# SCH_spponpcbfin_2024-06-20.net
KiCad netlist of a schematic drawn in EasyEDA
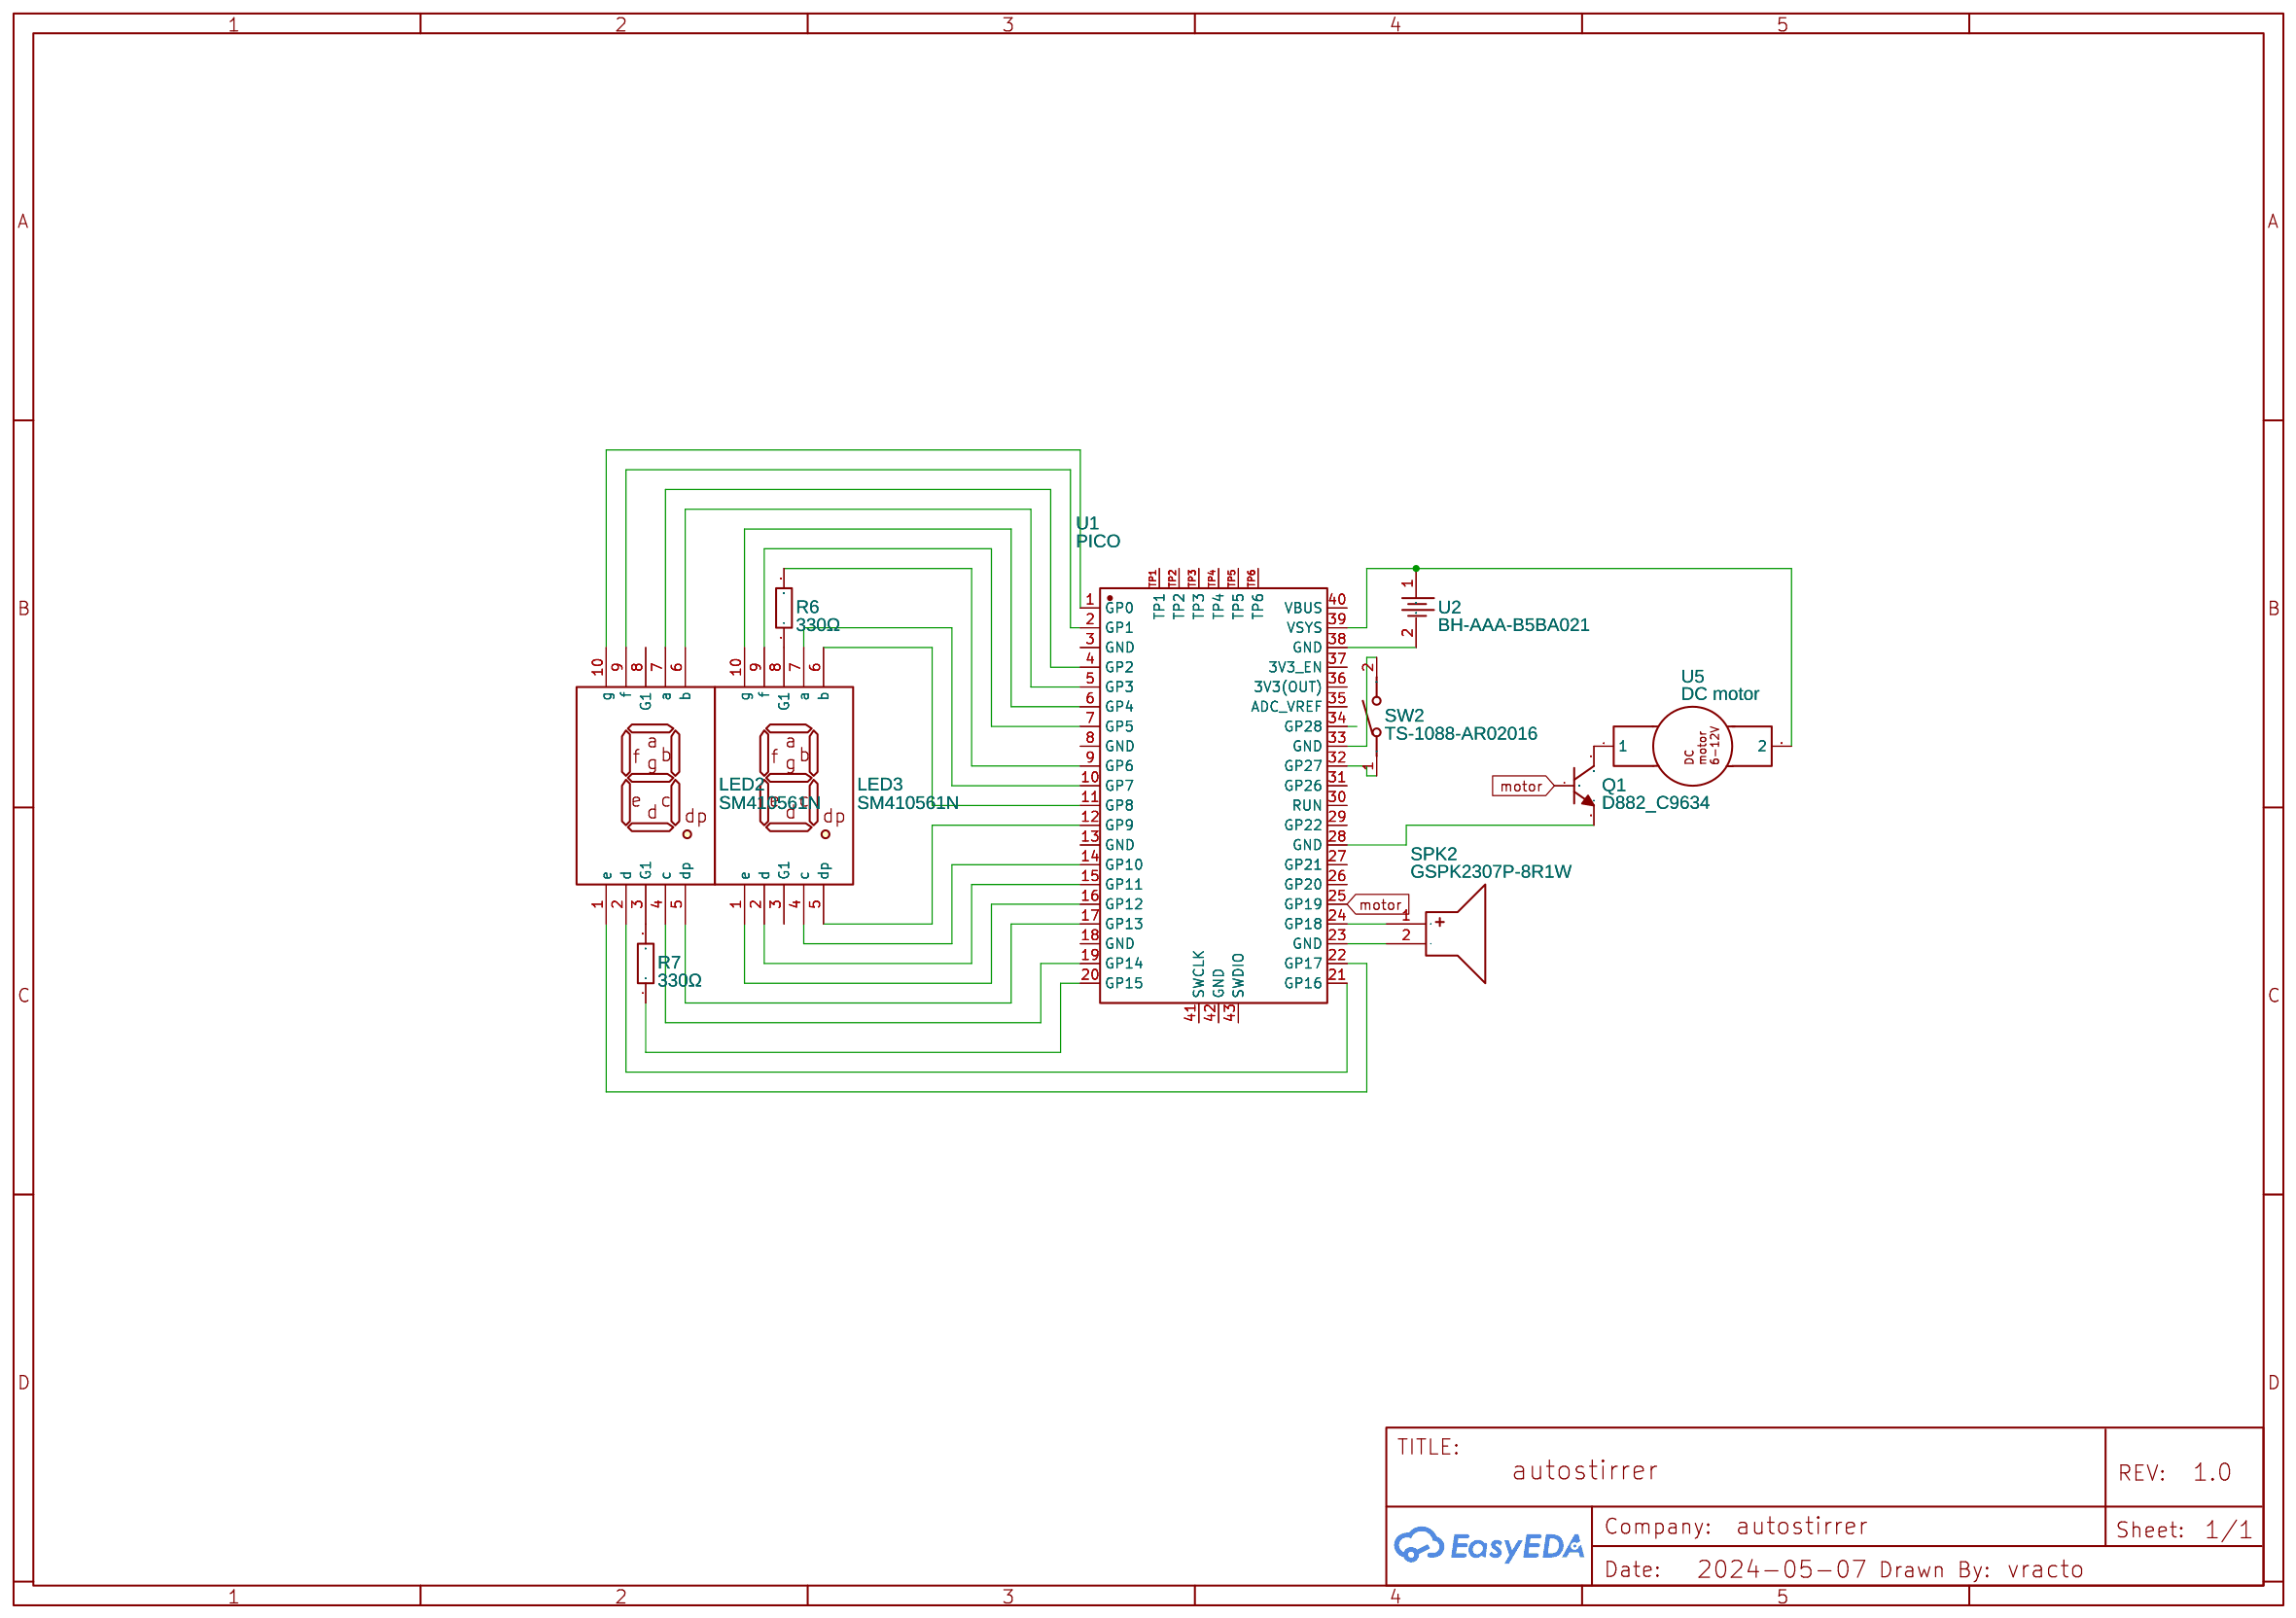
[diagram p0: schematic sheet]

(export (version "E")
  (design (tool "Eeschema 10.0.6"))
  (components
    (comp (ref "LED2")
      (value "SM410561N")
      (fields (field (name "Manufacturer") "ARKLED(方舟)"))
      (libsource (lib "") (part "SM410561N"))
    )
    (comp (ref "LED3")
      (value "SM410561N")
      (fields (field (name "Manufacturer") "ARKLED(方舟)"))
      (libsource (lib "") (part "SM410561N"))
    )
    (comp (ref "Q1")
      (value "D882_C9634")
      (fields
        (field (name "Manufacturer Part") "D882 Y档160&#126;320")
        (field (name "Manufacturer") "CJ(江苏长电/长晶)")
      )
      (libsource (lib "") (part "D882_C9634"))
    )
    (comp (ref "R6")
      (value "330Ω")
      (fields (field (name "Manufacturer Part") "MFR-25FTE52-330R") (field (name "Manufacturer") "YAGEO(国巨)"))
      (libsource (lib "") (part "MFR-25FTE52-330R"))
    )
    (comp (ref "R7")
      (value "330Ω")
      (fields (field (name "Manufacturer Part") "MFR-25FTE52-330R") (field (name "Manufacturer") "YAGEO(国巨)"))
      (libsource (lib "") (part "MFR-25FTE52-330R"))
    )
    (comp (ref "SPK2")
      (value "GSPK2307P-8R1W")
      (fields (field (name "Manufacturer") "INGHAi(赢海)"))
      (libsource (lib "") (part "GSPK2307P-8R1W"))
    )
    (comp (ref "SW2")
      (value "TS-1088-AR02016")
      (fields (field (name "Manufacturer") "XUNPU(讯普)"))
      (libsource (lib "") (part "TS-1088-AR02016"))
    )
    (comp (ref "U1")
      (value "PICO")
      (fields (field (name "Manufacturer") "Raspberry Pi(树莓派)"))
      (libsource (lib "") (part "PICO"))
    )
    (comp (ref "U2")
      (value "BH-AAA-B5BA021")
      (fields (field (name "Manufacturer") "MYOUNG(美阳)"))
      (libsource (lib "") (part "BH-AAA-B5BA021"))
    )
    (comp (ref "U5")
      (value "DC motor")
      (fields (field (name "Manufacturer Part") "?"))
      (libsource (lib "") (part "Unknown_850_-435"))
    )
  )
  (nets
    (net (code "1") (name "Net-(LED2-G1-Pad3)") (class "Default")
      (node (ref "LED2") (pin "3") (pinfunction "G1_3") (pintype "input"))
      (node (ref "R7") (pin "2") (pinfunction "2_2") (pintype "input"))
    )
    (net (code "2") (name "Net-(LED2-a)") (class "Default")
      (node (ref "LED2") (pin "7") (pinfunction "a_7") (pintype "input"))
      (node (ref "U1") (pin "4") (pinfunction "GP2_4") (pintype "unspecified"))
    )
    (net (code "3") (name "Net-(LED2-b)") (class "Default")
      (node (ref "LED2") (pin "6") (pinfunction "b_6") (pintype "input"))
      (node (ref "U1") (pin "5") (pinfunction "GP3_5") (pintype "unspecified"))
    )
    (net (code "4") (name "Net-(LED2-c)") (class "Default")
      (node (ref "LED2") (pin "4") (pinfunction "c_4") (pintype "input"))
      (node (ref "U1") (pin "19") (pinfunction "GP14_19") (pintype "unspecified"))
    )
    (net (code "5") (name "Net-(LED2-d)") (class "Default")
      (node (ref "LED2") (pin "2") (pinfunction "d_2") (pintype "input"))
      (node (ref "U1") (pin "21") (pinfunction "GP16_21") (pintype "unspecified"))
    )
    (net (code "6") (name "Net-(LED2-dp)") (class "Default")
      (node (ref "LED2") (pin "5") (pinfunction "dp_5") (pintype "input"))
      (node (ref "U1") (pin "17") (pinfunction "GP13_17") (pintype "unspecified"))
    )
    (net (code "7") (name "Net-(LED2-e)") (class "Default")
      (node (ref "LED2") (pin "1") (pinfunction "e_1") (pintype "input"))
      (node (ref "U1") (pin "22") (pinfunction "GP17_22") (pintype "unspecified"))
    )
    (net (code "8") (name "Net-(LED2-f)") (class "Default")
      (node (ref "LED2") (pin "9") (pinfunction "f_9") (pintype "input"))
      (node (ref "U1") (pin "2") (pinfunction "GP1_2") (pintype "unspecified"))
    )
    (net (code "9") (name "Net-(LED2-g)") (class "Default")
      (node (ref "LED2") (pin "10") (pinfunction "g_10") (pintype "input"))
      (node (ref "U1") (pin "1") (pinfunction "GP0_1") (pintype "unspecified"))
    )
    (net (code "10") (name "Net-(LED3-G1-Pad8)") (class "Default")
      (node (ref "LED3") (pin "8") (pinfunction "G1_8") (pintype "input"))
      (node (ref "R6") (pin "1") (pinfunction "1_1") (pintype "input"))
    )
    (net (code "11") (name "Net-(LED3-a)") (class "Default")
      (node (ref "LED3") (pin "7") (pinfunction "a_7") (pintype "input"))
      (node (ref "U1") (pin "10") (pinfunction "GP7_10") (pintype "unspecified"))
    )
    (net (code "12") (name "Net-(LED3-b)") (class "Default")
      (node (ref "LED3") (pin "6") (pinfunction "b_6") (pintype "input"))
      (node (ref "U1") (pin "11") (pinfunction "GP8_11") (pintype "unspecified"))
    )
    (net (code "13") (name "Net-(LED3-c)") (class "Default")
      (node (ref "LED3") (pin "4") (pinfunction "c_4") (pintype "input"))
      (node (ref "U1") (pin "14") (pinfunction "GP10_14") (pintype "unspecified"))
    )
    (net (code "14") (name "Net-(LED3-d)") (class "Default")
      (node (ref "LED3") (pin "2") (pinfunction "d_2") (pintype "input"))
      (node (ref "U1") (pin "15") (pinfunction "GP11_15") (pintype "unspecified"))
    )
    (net (code "15") (name "Net-(LED3-dp)") (class "Default")
      (node (ref "LED3") (pin "5") (pinfunction "dp_5") (pintype "input"))
      (node (ref "U1") (pin "12") (pinfunction "GP9_12") (pintype "unspecified"))
    )
    (net (code "16") (name "Net-(LED3-e)") (class "Default")
      (node (ref "LED3") (pin "1") (pinfunction "e_1") (pintype "input"))
      (node (ref "U1") (pin "16") (pinfunction "GP12_16") (pintype "unspecified"))
    )
    (net (code "17") (name "Net-(LED3-f)") (class "Default")
      (node (ref "LED3") (pin "9") (pinfunction "f_9") (pintype "input"))
      (node (ref "U1") (pin "7") (pinfunction "GP5_7") (pintype "unspecified"))
    )
    (net (code "18") (name "Net-(LED3-g)") (class "Default")
      (node (ref "LED3") (pin "10") (pinfunction "g_10") (pintype "input"))
      (node (ref "U1") (pin "6") (pinfunction "GP4_6") (pintype "unspecified"))
    )
    (net (code "19") (name "Net-(Q1-C)") (class "Default")
      (node (ref "Q1") (pin "2") (pinfunction "C_2") (pintype "input"))
      (node (ref "U5") (pin "1") (pinfunction "1_1") (pintype "unspecified"))
    )
    (net (code "20") (name "Net-(Q1-E)") (class "Default")
      (node (ref "Q1") (pin "3") (pinfunction "E_3") (pintype "input"))
      (node (ref "U1") (pin "28") (pinfunction "GND_28") (pintype "unspecified"))
    )
    (net (code "21") (name "Net-(SPK2-+)") (class "Default")
      (node (ref "SPK2") (pin "1") (pinfunction "+_1") (pintype "unspecified"))
      (node (ref "U1") (pin "24") (pinfunction "GP18_24") (pintype "unspecified"))
    )
    (net (code "22") (name "Net-(SPK2--)") (class "Default")
      (node (ref "SPK2") (pin "2") (pinfunction "-_2") (pintype "unspecified"))
      (node (ref "U1") (pin "23") (pinfunction "GND_23") (pintype "unspecified"))
    )
    (net (code "23") (name "Net-(SW2-Pad2)") (class "Default")
      (node (ref "SW2") (pin "2") (pinfunction "2_2") (pintype "unspecified"))
      (node (ref "U1") (pin "33") (pinfunction "GND_33") (pintype "unspecified"))
    )
    (net (code "24") (name "Net-(U1-GND-Pad38)") (class "Default")
      (node (ref "U1") (pin "38") (pinfunction "GND_38") (pintype "unspecified"))
      (node (ref "U2") (pin "2") (pinfunction "2_2") (pintype "input"))
    )
    (net (code "25") (name "Net-(U1-GP6)") (class "Default")
      (node (ref "R6") (pin "2") (pinfunction "2_2") (pintype "input"))
      (node (ref "U1") (pin "9") (pinfunction "GP6_9") (pintype "unspecified"))
    )
    (net (code "26") (name "Net-(U1-GP15)") (class "Default")
      (node (ref "R7") (pin "1") (pinfunction "1_1") (pintype "input"))
      (node (ref "U1") (pin "20") (pinfunction "GP15_20") (pintype "unspecified"))
    )
    (net (code "27") (name "Net-(U1-GP27)") (class "Default")
      (node (ref "SW2") (pin "1") (pinfunction "1_1") (pintype "unspecified"))
      (node (ref "U1") (pin "32") (pinfunction "GP27_32") (pintype "unspecified"))
    )
    (net (code "28") (name "Net-(U1-VSYS)") (class "Default")
      (node (ref "U1") (pin "39") (pinfunction "VSYS_39") (pintype "unspecified"))
      (node (ref "U2") (pin "1") (pinfunction "1_1") (pintype "input"))
      (node (ref "U5") (pin "2") (pinfunction "2_2") (pintype "unspecified"))
    )
    (net (code "29") (name "motor") (class "Default")
      (node (ref "Q1") (pin "1") (pinfunction "B_1") (pintype "input"))
      (node (ref "U1") (pin "25") (pinfunction "GP19_25") (pintype "unspecified"))
    )
    (net (code "30") (name "unconnected-(LED2-G1-Pad8)") (class "Default")
      (node (ref "LED2") (pin "8") (pinfunction "G1_8") (pintype "input"))
    )
    (net (code "31") (name "unconnected-(LED3-G1-Pad3)") (class "Default")
      (node (ref "LED3") (pin "3") (pinfunction "G1_3") (pintype "input"))
    )
    (net (code "32") (name "unconnected-(U1-3V3(OUT)-Pad36)") (class "Default")
      (node (ref "U1") (pin "36") (pinfunction "3V3(OUT)_36") (pintype "unspecified"))
    )
    (net (code "33") (name "unconnected-(U1-3V3_EN-Pad37)") (class "Default")
      (node (ref "U1") (pin "37") (pinfunction "3V3_EN_37") (pintype "unspecified"))
    )
    (net (code "34") (name "unconnected-(U1-ADC_VREF-Pad35)") (class "Default")
      (node (ref "U1") (pin "35") (pinfunction "ADC_VREF_35") (pintype "unspecified"))
    )
    (net (code "35") (name "unconnected-(U1-GND-Pad3)") (class "Default")
      (node (ref "U1") (pin "3") (pinfunction "GND_3") (pintype "unspecified"))
    )
    (net (code "36") (name "unconnected-(U1-GND-Pad8)") (class "Default")
      (node (ref "U1") (pin "8") (pinfunction "GND_8") (pintype "unspecified"))
    )
    (net (code "37") (name "unconnected-(U1-GND-Pad13)") (class "Default")
      (node (ref "U1") (pin "13") (pinfunction "GND_13") (pintype "unspecified"))
    )
    (net (code "38") (name "unconnected-(U1-GND-Pad18)") (class "Default")
      (node (ref "U1") (pin "18") (pinfunction "GND_18") (pintype "unspecified"))
    )
    (net (code "39") (name "unconnected-(U1-GND-Pad42)") (class "Default")
      (node (ref "U1") (pin "42") (pinfunction "GND_42") (pintype "unspecified"))
    )
    (net (code "40") (name "unconnected-(U1-GP20-Pad26)") (class "Default")
      (node (ref "U1") (pin "26") (pinfunction "GP20_26") (pintype "unspecified"))
    )
    (net (code "41") (name "unconnected-(U1-GP21-Pad27)") (class "Default")
      (node (ref "U1") (pin "27") (pinfunction "GP21_27") (pintype "unspecified"))
    )
    (net (code "42") (name "unconnected-(U1-GP22-Pad29)") (class "Default")
      (node (ref "U1") (pin "29") (pinfunction "GP22_29") (pintype "unspecified"))
    )
    (net (code "43") (name "unconnected-(U1-GP26-Pad31)") (class "Default")
      (node (ref "U1") (pin "31") (pinfunction "GP26_31") (pintype "unspecified"))
    )
    (net (code "44") (name "unconnected-(U1-GP28-Pad34)") (class "Default")
      (node (ref "U1") (pin "34") (pinfunction "GP28_34") (pintype "unspecified"))
    )
    (net (code "45") (name "unconnected-(U1-PadTP1)") (class "Default")
      (node (ref "U1") (pin "TP1") (pinfunction "TP1_TP1") (pintype "unspecified"))
    )
    (net (code "46") (name "unconnected-(U1-PadTP2)") (class "Default")
      (node (ref "U1") (pin "TP2") (pinfunction "TP2_TP2") (pintype "unspecified"))
    )
    (net (code "47") (name "unconnected-(U1-PadTP3)") (class "Default")
      (node (ref "U1") (pin "TP3") (pinfunction "TP3_TP3") (pintype "unspecified"))
    )
    (net (code "48") (name "unconnected-(U1-PadTP4)") (class "Default")
      (node (ref "U1") (pin "TP4") (pinfunction "TP4_TP4") (pintype "unspecified"))
    )
    (net (code "49") (name "unconnected-(U1-PadTP5)") (class "Default")
      (node (ref "U1") (pin "TP5") (pinfunction "TP5_TP5") (pintype "unspecified"))
    )
    (net (code "50") (name "unconnected-(U1-PadTP6)") (class "Default")
      (node (ref "U1") (pin "TP6") (pinfunction "TP6_TP6") (pintype "unspecified"))
    )
    (net (code "51") (name "unconnected-(U1-RUN-Pad30)") (class "Default")
      (node (ref "U1") (pin "30") (pinfunction "RUN_30") (pintype "unspecified"))
    )
    (net (code "52") (name "unconnected-(U1-SWCLK-Pad41)") (class "Default")
      (node (ref "U1") (pin "41") (pinfunction "SWCLK_41") (pintype "unspecified"))
    )
    (net (code "53") (name "unconnected-(U1-SWDIO-Pad43)") (class "Default")
      (node (ref "U1") (pin "43") (pinfunction "SWDIO_43") (pintype "unspecified"))
    )
    (net (code "54") (name "unconnected-(U1-VBUS-Pad40)") (class "Default")
      (node (ref "U1") (pin "40") (pinfunction "VBUS_40") (pintype "unspecified"))
    )
  )
)
